# mainModule.net
KiCad netlist of a schematic drawn in EAGLE
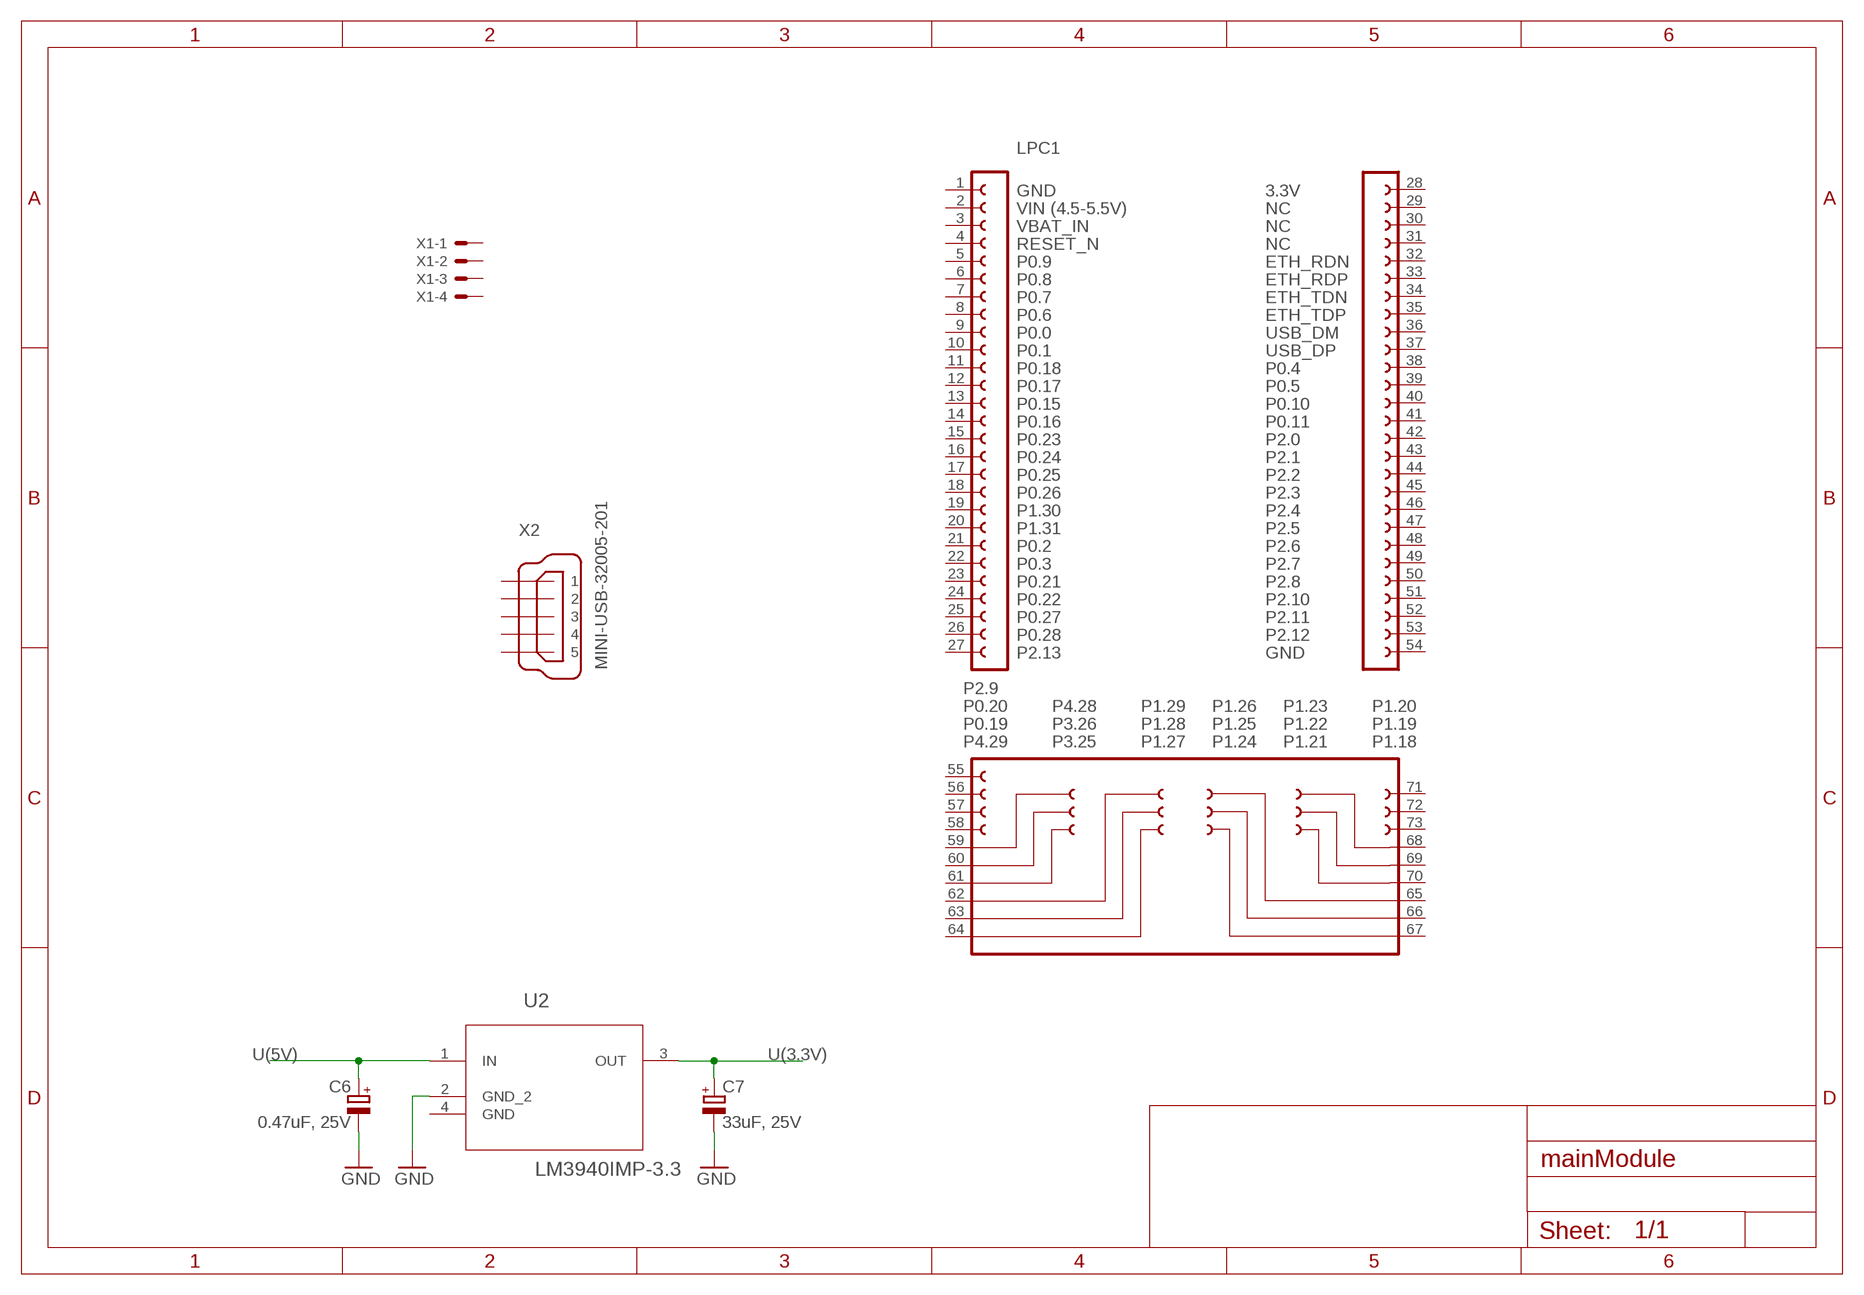
[diagram p0: schematic, sheet 1]

(export (version "E")
  (design (tool "Eeschema 10.0.6"))
  (components
    (comp (ref "C6")
      (value "0.47uF, 25V")
      (footprint "eagle-import:PANASONIC_C")
      (libsource (lib "eagle-import") (part "CPOL-EUC"))
    )
    (comp (ref "C7")
      (value "33uF, 25V")
      (footprint "eagle-import:PANASONIC_C")
      (libsource (lib "eagle-import") (part "CPOL-EUC"))
    )
    (comp (ref "LPC1")
      (value "LPCXPRESSO_LPC1769")
      (footprint "eagle-import:LPCXPRESSO_LPC1769")
      (libsource (lib "eagle-import") (part "LPCXPRESSO_LPC1769"))
    )
    (comp (ref "U2")
      (value "LM3940IMP-3.3")
      (footprint "eagle-import:SOT230P696X180-4N")
      (fields (field (name "MPN") "LM3940IMP-33"))
      (libsource (lib "eagle-import") (part "LM3940IMP-3.3"))
    )
    (comp (ref "X1")
      (value "KK-156-4")
      (footprint "eagle-import:KK-156-4")
      (libsource (lib "eagle-import") (part "KK-156-4"))
    )
    (comp (ref "X2")
      (value "MINI-USB-32005-201")
      (footprint "eagle-import:32005-201")
      (libsource (lib "eagle-import") (part "MINI-USB-32005-201"))
    )
  )
  (nets
    (net (code "1") (name "/U(3.3V)") (class "Default")
      (node (ref "C7") (pin "+") (pinfunction "+_+") (pintype "passive"))
      (node (ref "U2") (pin "3") (pinfunction "OUT_3") (pintype "output"))
    )
    (net (code "2") (name "/U(5V)") (class "Default")
      (node (ref "C6") (pin "+") (pinfunction "+_+") (pintype "passive"))
      (node (ref "U2") (pin "1") (pinfunction "IN_1") (pintype "power_in"))
    )
    (net (code "3") (name "GND") (class "Default")
      (node (ref "C6") (pin "-") (pinfunction "-_-") (pintype "passive"))
      (node (ref "C7") (pin "-") (pinfunction "-_-") (pintype "passive"))
      (node (ref "U2") (pin "2") (pinfunction "GND_2_2") (pintype "passive"))
    )
    (net (code "4") (name "unconnected-(LPC1-Pad1)") (class "Default")
      (node (ref "LPC1") (pin "1") (pinfunction "1_1") (pintype "passive"))
    )
    (net (code "5") (name "unconnected-(LPC1-Pad2)") (class "Default")
      (node (ref "LPC1") (pin "2") (pinfunction "2_2") (pintype "passive"))
    )
    (net (code "6") (name "unconnected-(LPC1-Pad3)") (class "Default")
      (node (ref "LPC1") (pin "3") (pinfunction "3_3") (pintype "passive"))
    )
    (net (code "7") (name "unconnected-(LPC1-Pad4)") (class "Default")
      (node (ref "LPC1") (pin "4") (pinfunction "4_4") (pintype "passive"))
    )
    (net (code "8") (name "unconnected-(LPC1-Pad5)") (class "Default")
      (node (ref "LPC1") (pin "5") (pinfunction "5_5") (pintype "passive"))
    )
    (net (code "9") (name "unconnected-(LPC1-Pad6)") (class "Default")
      (node (ref "LPC1") (pin "6") (pinfunction "6_6") (pintype "passive"))
    )
    (net (code "10") (name "unconnected-(LPC1-Pad7)") (class "Default")
      (node (ref "LPC1") (pin "7") (pinfunction "7_7") (pintype "passive"))
    )
    (net (code "11") (name "unconnected-(LPC1-Pad8)") (class "Default")
      (node (ref "LPC1") (pin "8") (pinfunction "8_8") (pintype "passive"))
    )
    (net (code "12") (name "unconnected-(LPC1-Pad9)") (class "Default")
      (node (ref "LPC1") (pin "9") (pinfunction "9_9") (pintype "passive"))
    )
    (net (code "13") (name "unconnected-(LPC1-Pad10)") (class "Default")
      (node (ref "LPC1") (pin "10") (pinfunction "10_10") (pintype "passive"))
    )
    (net (code "14") (name "unconnected-(LPC1-Pad11)") (class "Default")
      (node (ref "LPC1") (pin "11") (pinfunction "11_11") (pintype "passive"))
    )
    (net (code "15") (name "unconnected-(LPC1-Pad12)") (class "Default")
      (node (ref "LPC1") (pin "12") (pinfunction "12_12") (pintype "passive"))
    )
    (net (code "16") (name "unconnected-(LPC1-Pad13)") (class "Default")
      (node (ref "LPC1") (pin "13") (pinfunction "13_13") (pintype "passive"))
    )
    (net (code "17") (name "unconnected-(LPC1-Pad14)") (class "Default")
      (node (ref "LPC1") (pin "14") (pinfunction "14_14") (pintype "passive"))
    )
    (net (code "18") (name "unconnected-(LPC1-Pad15)") (class "Default")
      (node (ref "LPC1") (pin "15") (pinfunction "15_15") (pintype "passive"))
    )
    (net (code "19") (name "unconnected-(LPC1-Pad16)") (class "Default")
      (node (ref "LPC1") (pin "16") (pinfunction "16_16") (pintype "passive"))
    )
    (net (code "20") (name "unconnected-(LPC1-Pad17)") (class "Default")
      (node (ref "LPC1") (pin "17") (pinfunction "17_17") (pintype "passive"))
    )
    (net (code "21") (name "unconnected-(LPC1-Pad18)") (class "Default")
      (node (ref "LPC1") (pin "18") (pinfunction "18_18") (pintype "passive"))
    )
    (net (code "22") (name "unconnected-(LPC1-Pad19)") (class "Default")
      (node (ref "LPC1") (pin "19") (pinfunction "19_19") (pintype "passive"))
    )
    (net (code "23") (name "unconnected-(LPC1-Pad20)") (class "Default")
      (node (ref "LPC1") (pin "20") (pinfunction "20_20") (pintype "passive"))
    )
    (net (code "24") (name "unconnected-(LPC1-Pad21)") (class "Default")
      (node (ref "LPC1") (pin "21") (pinfunction "21_21") (pintype "passive"))
    )
    (net (code "25") (name "unconnected-(LPC1-Pad22)") (class "Default")
      (node (ref "LPC1") (pin "22") (pinfunction "22_22") (pintype "passive"))
    )
    (net (code "26") (name "unconnected-(LPC1-Pad23)") (class "Default")
      (node (ref "LPC1") (pin "23") (pinfunction "23_23") (pintype "passive"))
    )
    (net (code "27") (name "unconnected-(LPC1-Pad24)") (class "Default")
      (node (ref "LPC1") (pin "24") (pinfunction "24_24") (pintype "passive"))
    )
    (net (code "28") (name "unconnected-(LPC1-Pad25)") (class "Default")
      (node (ref "LPC1") (pin "25") (pinfunction "25_25") (pintype "passive"))
    )
    (net (code "29") (name "unconnected-(LPC1-Pad26)") (class "Default")
      (node (ref "LPC1") (pin "26") (pinfunction "26_26") (pintype "passive"))
    )
    (net (code "30") (name "unconnected-(LPC1-Pad27)") (class "Default")
      (node (ref "LPC1") (pin "27") (pinfunction "27_27") (pintype "passive"))
    )
    (net (code "31") (name "unconnected-(LPC1-Pad28)") (class "Default")
      (node (ref "LPC1") (pin "28") (pinfunction "28_28") (pintype "passive"))
    )
    (net (code "32") (name "unconnected-(LPC1-Pad29)") (class "Default")
      (node (ref "LPC1") (pin "29") (pinfunction "29_29") (pintype "passive"))
    )
    (net (code "33") (name "unconnected-(LPC1-Pad30)") (class "Default")
      (node (ref "LPC1") (pin "30") (pinfunction "30_30") (pintype "passive"))
    )
    (net (code "34") (name "unconnected-(LPC1-Pad31)") (class "Default")
      (node (ref "LPC1") (pin "31") (pinfunction "31_31") (pintype "passive"))
    )
    (net (code "35") (name "unconnected-(LPC1-Pad32)") (class "Default")
      (node (ref "LPC1") (pin "32") (pinfunction "32_32") (pintype "passive"))
    )
    (net (code "36") (name "unconnected-(LPC1-Pad33)") (class "Default")
      (node (ref "LPC1") (pin "33") (pinfunction "33_33") (pintype "passive"))
    )
    (net (code "37") (name "unconnected-(LPC1-Pad34)") (class "Default")
      (node (ref "LPC1") (pin "34") (pinfunction "34_34") (pintype "passive"))
    )
    (net (code "38") (name "unconnected-(LPC1-Pad35)") (class "Default")
      (node (ref "LPC1") (pin "35") (pinfunction "35_35") (pintype "passive"))
    )
    (net (code "39") (name "unconnected-(LPC1-Pad36)") (class "Default")
      (node (ref "LPC1") (pin "36") (pinfunction "36_36") (pintype "passive"))
    )
    (net (code "40") (name "unconnected-(LPC1-Pad37)") (class "Default")
      (node (ref "LPC1") (pin "37") (pinfunction "37_37") (pintype "passive"))
    )
    (net (code "41") (name "unconnected-(LPC1-Pad38)") (class "Default")
      (node (ref "LPC1") (pin "38") (pinfunction "38_38") (pintype "passive"))
    )
    (net (code "42") (name "unconnected-(LPC1-Pad39)") (class "Default")
      (node (ref "LPC1") (pin "39") (pinfunction "39_39") (pintype "passive"))
    )
    (net (code "43") (name "unconnected-(LPC1-Pad40)") (class "Default")
      (node (ref "LPC1") (pin "40") (pinfunction "40_40") (pintype "passive"))
    )
    (net (code "44") (name "unconnected-(LPC1-Pad41)") (class "Default")
      (node (ref "LPC1") (pin "41") (pinfunction "41_41") (pintype "passive"))
    )
    (net (code "45") (name "unconnected-(LPC1-Pad42)") (class "Default")
      (node (ref "LPC1") (pin "42") (pinfunction "42_42") (pintype "passive"))
    )
    (net (code "46") (name "unconnected-(LPC1-Pad43)") (class "Default")
      (node (ref "LPC1") (pin "43") (pinfunction "43_43") (pintype "passive"))
    )
    (net (code "47") (name "unconnected-(LPC1-Pad44)") (class "Default")
      (node (ref "LPC1") (pin "44") (pinfunction "44_44") (pintype "passive"))
    )
    (net (code "48") (name "unconnected-(LPC1-Pad45)") (class "Default")
      (node (ref "LPC1") (pin "45") (pinfunction "45_45") (pintype "passive"))
    )
    (net (code "49") (name "unconnected-(LPC1-Pad46)") (class "Default")
      (node (ref "LPC1") (pin "46") (pinfunction "46_46") (pintype "passive"))
    )
    (net (code "50") (name "unconnected-(LPC1-Pad47)") (class "Default")
      (node (ref "LPC1") (pin "47") (pinfunction "47_47") (pintype "passive"))
    )
    (net (code "51") (name "unconnected-(LPC1-Pad48)") (class "Default")
      (node (ref "LPC1") (pin "48") (pinfunction "48_48") (pintype "passive"))
    )
    (net (code "52") (name "unconnected-(LPC1-Pad49)") (class "Default")
      (node (ref "LPC1") (pin "49") (pinfunction "49_49") (pintype "passive"))
    )
    (net (code "53") (name "unconnected-(LPC1-Pad50)") (class "Default")
      (node (ref "LPC1") (pin "50") (pinfunction "50_50") (pintype "passive"))
    )
    (net (code "54") (name "unconnected-(LPC1-Pad51)") (class "Default")
      (node (ref "LPC1") (pin "51") (pinfunction "51_51") (pintype "passive"))
    )
    (net (code "55") (name "unconnected-(LPC1-Pad52)") (class "Default")
      (node (ref "LPC1") (pin "52") (pinfunction "52_52") (pintype "passive"))
    )
    (net (code "56") (name "unconnected-(LPC1-Pad53)") (class "Default")
      (node (ref "LPC1") (pin "53") (pinfunction "53_53") (pintype "passive"))
    )
    (net (code "57") (name "unconnected-(LPC1-Pad54)") (class "Default")
      (node (ref "LPC1") (pin "54") (pinfunction "54_54") (pintype "passive"))
    )
    (net (code "58") (name "unconnected-(LPC1-Pad55)") (class "Default")
      (node (ref "LPC1") (pin "55") (pinfunction "55_55") (pintype "passive"))
    )
    (net (code "59") (name "unconnected-(LPC1-Pad56)") (class "Default")
      (node (ref "LPC1") (pin "56") (pinfunction "56_56") (pintype "passive"))
    )
    (net (code "60") (name "unconnected-(LPC1-Pad57)") (class "Default")
      (node (ref "LPC1") (pin "57") (pinfunction "57_57") (pintype "passive"))
    )
    (net (code "61") (name "unconnected-(LPC1-Pad58)") (class "Default")
      (node (ref "LPC1") (pin "58") (pinfunction "58_58") (pintype "passive"))
    )
    (net (code "62") (name "unconnected-(LPC1-Pad59)") (class "Default")
      (node (ref "LPC1") (pin "59") (pinfunction "59_59") (pintype "passive"))
    )
    (net (code "63") (name "unconnected-(LPC1-Pad60)") (class "Default")
      (node (ref "LPC1") (pin "60") (pinfunction "60_60") (pintype "passive"))
    )
    (net (code "64") (name "unconnected-(LPC1-Pad61)") (class "Default")
      (node (ref "LPC1") (pin "61") (pinfunction "61_61") (pintype "passive"))
    )
    (net (code "65") (name "unconnected-(LPC1-Pad62)") (class "Default")
      (node (ref "LPC1") (pin "62") (pinfunction "62_62") (pintype "passive"))
    )
    (net (code "66") (name "unconnected-(LPC1-Pad63)") (class "Default")
      (node (ref "LPC1") (pin "63") (pinfunction "63_63") (pintype "passive"))
    )
    (net (code "67") (name "unconnected-(LPC1-Pad64)") (class "Default")
      (node (ref "LPC1") (pin "64") (pinfunction "64_64") (pintype "passive"))
    )
    (net (code "68") (name "unconnected-(LPC1-Pad65)") (class "Default")
      (node (ref "LPC1") (pin "65") (pinfunction "65_65") (pintype "passive"))
    )
    (net (code "69") (name "unconnected-(LPC1-Pad66)") (class "Default")
      (node (ref "LPC1") (pin "66") (pinfunction "66_66") (pintype "passive"))
    )
    (net (code "70") (name "unconnected-(LPC1-Pad67)") (class "Default")
      (node (ref "LPC1") (pin "67") (pinfunction "67_67") (pintype "passive"))
    )
    (net (code "71") (name "unconnected-(LPC1-Pad68)") (class "Default")
      (node (ref "LPC1") (pin "68") (pinfunction "68_68") (pintype "passive"))
    )
    (net (code "72") (name "unconnected-(LPC1-Pad69)") (class "Default")
      (node (ref "LPC1") (pin "69") (pinfunction "69_69") (pintype "passive"))
    )
    (net (code "73") (name "unconnected-(LPC1-Pad70)") (class "Default")
      (node (ref "LPC1") (pin "70") (pinfunction "70_70") (pintype "passive"))
    )
    (net (code "74") (name "unconnected-(LPC1-Pad71)") (class "Default")
      (node (ref "LPC1") (pin "71") (pinfunction "71_71") (pintype "passive"))
    )
    (net (code "75") (name "unconnected-(LPC1-Pad72)") (class "Default")
      (node (ref "LPC1") (pin "72") (pinfunction "72_72") (pintype "passive"))
    )
    (net (code "76") (name "unconnected-(LPC1-Pad73)") (class "Default")
      (node (ref "LPC1") (pin "73") (pinfunction "73_73") (pintype "passive"))
    )
    (net (code "77") (name "unconnected-(U2-GND-Pad4)") (class "Default")
      (node (ref "U2") (pin "4") (pinfunction "GND_4") (pintype "passive"))
    )
    (net (code "78") (name "unconnected-(X1A-S-Pad1)") (class "Default")
      (node (ref "X1") (pin "1") (pinfunction "S_1") (pintype "passive"))
    )
    (net (code "79") (name "unconnected-(X1B-S-Pad2)") (class "Default")
      (node (ref "X1") (pin "2") (pinfunction "S_2") (pintype "passive"))
    )
    (net (code "80") (name "unconnected-(X1C-S-Pad3)") (class "Default")
      (node (ref "X1") (pin "3") (pinfunction "S_3") (pintype "passive"))
    )
    (net (code "81") (name "unconnected-(X1D-S-Pad4)") (class "Default")
      (node (ref "X1") (pin "4") (pinfunction "S_4") (pintype "passive"))
    )
    (net (code "82") (name "unconnected-(X2-Pad1)") (class "Default")
      (node (ref "X2") (pin "1") (pinfunction "1_1") (pintype "passive"))
    )
    (net (code "83") (name "unconnected-(X2-Pad2)") (class "Default")
      (node (ref "X2") (pin "2") (pinfunction "2_2") (pintype "passive"))
    )
    (net (code "84") (name "unconnected-(X2-Pad3)") (class "Default")
      (node (ref "X2") (pin "3") (pinfunction "3_3") (pintype "passive"))
    )
    (net (code "85") (name "unconnected-(X2-Pad4)") (class "Default")
      (node (ref "X2") (pin "4") (pinfunction "4_4") (pintype "passive"))
    )
    (net (code "86") (name "unconnected-(X2-Pad5)") (class "Default")
      (node (ref "X2") (pin "5") (pinfunction "5_5") (pintype "passive"))
    )
  )
)
